# 74.net
KiCad netlist of a schematic drawn in EAGLE
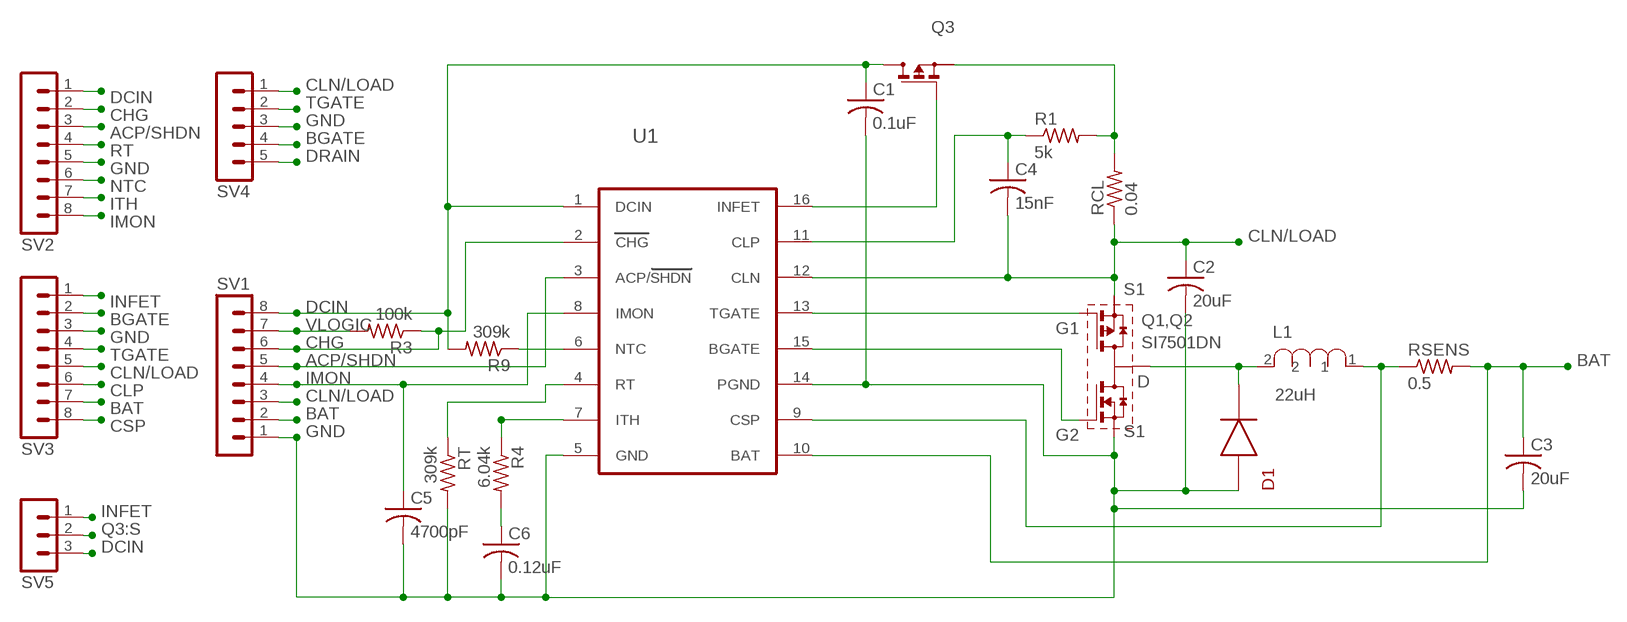
[diagram p0: schematic, sheet 1]

(export (version "E")
  (design (tool "Eeschema 10.0.6"))
  (components
    (comp (ref "C1")
      (value "0.1uF")
      (footprint "eagle-import:C1210")
      (libsource (lib "eagle-import") (part "C-USC1210"))
    )
    (comp (ref "C2")
      (value "20uF")
      (footprint "eagle-import:C1210")
      (libsource (lib "eagle-import") (part "C-USC1210"))
    )
    (comp (ref "C3")
      (value "20uF")
      (footprint "eagle-import:C1210")
      (libsource (lib "eagle-import") (part "C-USC1210"))
    )
    (comp (ref "C4")
      (value "15nF")
      (footprint "eagle-import:C1210")
      (libsource (lib "eagle-import") (part "C-USC1210"))
    )
    (comp (ref "C5")
      (value "4700pF")
      (footprint "eagle-import:C1210")
      (libsource (lib "eagle-import") (part "C-USC1210"))
    )
    (comp (ref "C6")
      (value "0.12uF")
      (footprint "eagle-import:C1210")
      (libsource (lib "eagle-import") (part "C-USC1210"))
    )
    (comp (ref "D1")
      (value "DIODE")
      (footprint "eagle-import:DIODE")
      (libsource (lib "eagle-import") (part "DIODE"))
    )
    (comp (ref "L1")
      (value "22uH")
      (footprint "eagle-import:POWERINDUCTOR")
      (libsource (lib "eagle-import") (part "SDR1005INDUCTOR"))
    )
    (comp (ref "Q1,Q2")
      (value "SI7501DN")
      (footprint "eagle-import:POWERPAK")
      (libsource (lib "eagle-import") (part "SI7501DN"))
    )
    (comp (ref "Q3")
      (value "MOSFET")
      (footprint "eagle-import:SOT-23")
      (libsource (lib "eagle-import") (part "MOSFET"))
    )
    (comp (ref "R1")
      (value "5k")
      (footprint "eagle-import:R1206")
      (libsource (lib "eagle-import") (part "R-US_R1206"))
    )
    (comp (ref "R3")
      (value "100k")
      (footprint "eagle-import:R1206")
      (libsource (lib "eagle-import") (part "R-US_R1206"))
    )
    (comp (ref "R4")
      (value "6.04k")
      (footprint "eagle-import:R1206")
      (libsource (lib "eagle-import") (part "R-US_R1206"))
    )
    (comp (ref "R9")
      (value "309k")
      (footprint "eagle-import:R1206")
      (libsource (lib "eagle-import") (part "R-US_R1206"))
    )
    (comp (ref "RCL")
      (value "0.04")
      (footprint "eagle-import:R1206")
      (libsource (lib "eagle-import") (part "R-US_R1206"))
    )
    (comp (ref "RSENS")
      (value "0.5")
      (footprint "eagle-import:0612_1632")
      (libsource (lib "eagle-import") (part "0612/1632"))
    )
    (comp (ref "RT")
      (value "309k")
      (footprint "eagle-import:R1206")
      (libsource (lib "eagle-import") (part "R-US_R1206"))
    )
    (comp (ref "SV1")
      (value "MA08-1")
      (footprint "eagle-import:MA08-1")
      (libsource (lib "eagle-import") (part "MA08-1"))
    )
    (comp (ref "SV2")
      (value "MA08-1")
      (footprint "eagle-import:MA08-1")
      (libsource (lib "eagle-import") (part "MA08-1"))
    )
    (comp (ref "SV3")
      (value "MA08-1")
      (footprint "eagle-import:MA08-1")
      (libsource (lib "eagle-import") (part "MA08-1"))
    )
    (comp (ref "SV4")
      (value "MA05-1")
      (footprint "eagle-import:MA05-1")
      (libsource (lib "eagle-import") (part "MA05-1"))
    )
    (comp (ref "SV5")
      (value "MA03-1")
      (footprint "eagle-import:MA03-1")
      (libsource (lib "eagle-import") (part "MA03-1"))
    )
    (comp (ref "U1")
      (value "LTC6004")
      (footprint "eagle-import:SSOP-16")
      (libsource (lib "eagle-import") (part "LTC6004"))
    )
  )
  (nets
    (net (code "1") (name "/ACP{slash}SHDN") (class "Default")
      (node (ref "SV1") (pin "5") (pinfunction "5_5") (pintype "passive"))
      (node (ref "SV2") (pin "3") (pinfunction "3_3") (pintype "passive"))
      (node (ref "U1") (pin "3") (pinfunction "ACP/SHDN_3") (pintype "power_in"))
    )
    (net (code "2") (name "/BAT") (class "Default")
      (node (ref "C3") (pin "1") (pinfunction "1_1") (pintype "passive"))
      (node (ref "RSENS") (pin "2") (pinfunction "2_2") (pintype "passive"))
      (node (ref "SV1") (pin "2") (pinfunction "2_2") (pintype "passive"))
      (node (ref "SV3") (pin "7") (pinfunction "7_7") (pintype "passive"))
      (node (ref "U1") (pin "10") (pinfunction "BAT_10") (pintype "power_in"))
    )
    (net (code "3") (name "/BGATE") (class "Default")
      (node (ref "Q1,Q2") (pin "G2") (pinfunction "G2_G2") (pintype "passive"))
      (node (ref "SV3") (pin "2") (pinfunction "2_2") (pintype "passive"))
      (node (ref "SV4") (pin "4") (pinfunction "4_4") (pintype "passive"))
      (node (ref "U1") (pin "15") (pinfunction "BGATE_15") (pintype "power_in"))
    )
    (net (code "4") (name "/CHG") (class "Default")
      (node (ref "R3") (pin "1") (pinfunction "1_1") (pintype "passive"))
      (node (ref "SV1") (pin "6") (pinfunction "6_6") (pintype "passive"))
      (node (ref "SV2") (pin "2") (pinfunction "2_2") (pintype "passive"))
      (node (ref "U1") (pin "2") (pinfunction "CHG_2") (pintype "power_in"))
    )
    (net (code "5") (name "/CLN{slash}LOAD") (class "Default")
      (node (ref "C2") (pin "1") (pinfunction "1_1") (pintype "passive"))
      (node (ref "C4") (pin "2") (pinfunction "2_2") (pintype "passive"))
      (node (ref "Q1,Q2") (pin "S1") (pinfunction "S1_S1") (pintype "passive"))
      (node (ref "RCL") (pin "1") (pinfunction "1_1") (pintype "passive"))
      (node (ref "SV1") (pin "3") (pinfunction "3_3") (pintype "passive"))
      (node (ref "SV3") (pin "5") (pinfunction "5_5") (pintype "passive"))
      (node (ref "SV4") (pin "1") (pinfunction "1_1") (pintype "passive"))
      (node (ref "U1") (pin "12") (pinfunction "CLN_12") (pintype "power_in"))
    )
    (net (code "6") (name "/CLP") (class "Default")
      (node (ref "C4") (pin "1") (pinfunction "1_1") (pintype "passive"))
      (node (ref "R1") (pin "1") (pinfunction "1_1") (pintype "passive"))
      (node (ref "SV3") (pin "6") (pinfunction "6_6") (pintype "passive"))
      (node (ref "U1") (pin "11") (pinfunction "CLP_11") (pintype "output"))
    )
    (net (code "7") (name "/CSP") (class "Default")
      (node (ref "L1") (pin "1") (pinfunction "1_1") (pintype "passive"))
      (node (ref "RSENS") (pin "1") (pinfunction "1_1") (pintype "passive"))
      (node (ref "SV3") (pin "8") (pinfunction "8_8") (pintype "passive"))
      (node (ref "U1") (pin "9") (pinfunction "CSP_9") (pintype "power_in"))
    )
    (net (code "8") (name "/DCIN") (class "Default")
      (node (ref "C1") (pin "1") (pinfunction "1_1") (pintype "passive"))
      (node (ref "Q3") (pin "DRAIN") (pinfunction "D_DRAIN") (pintype "passive"))
      (node (ref "R9") (pin "2") (pinfunction "2_2") (pintype "passive"))
      (node (ref "SV1") (pin "8") (pinfunction "8_8") (pintype "passive"))
      (node (ref "SV2") (pin "1") (pinfunction "1_1") (pintype "passive"))
      (node (ref "SV5") (pin "3") (pinfunction "3_3") (pintype "passive"))
      (node (ref "U1") (pin "1") (pinfunction "DCIN_1") (pintype "power_in"))
    )
    (net (code "9") (name "/DRAIN") (class "Default")
      (node (ref "D1") (pin "P$2") (pinfunction "2_P$2") (pintype "bidirectional"))
      (node (ref "L1") (pin "2") (pinfunction "2_2") (pintype "passive"))
      (node (ref "Q1,Q2") (pin "D") (pinfunction "D_D") (pintype "passive"))
      (node (ref "SV4") (pin "5") (pinfunction "5_5") (pintype "passive"))
    )
    (net (code "10") (name "/GND") (class "Default")
      (node (ref "C1") (pin "2") (pinfunction "2_2") (pintype "passive"))
      (node (ref "C2") (pin "2") (pinfunction "2_2") (pintype "passive"))
      (node (ref "C3") (pin "2") (pinfunction "2_2") (pintype "passive"))
      (node (ref "C5") (pin "2") (pinfunction "2_2") (pintype "passive"))
      (node (ref "C6") (pin "2") (pinfunction "2_2") (pintype "passive"))
      (node (ref "D1") (pin "P$1") (pinfunction "1_P$1") (pintype "bidirectional"))
      (node (ref "Q1,Q2") (pin "S2") (pinfunction "S2_S2") (pintype "passive"))
      (node (ref "RT") (pin "2") (pinfunction "2_2") (pintype "passive"))
      (node (ref "SV1") (pin "1") (pinfunction "1_1") (pintype "passive"))
      (node (ref "SV2") (pin "5") (pinfunction "5_5") (pintype "passive"))
      (node (ref "SV3") (pin "3") (pinfunction "3_3") (pintype "passive"))
      (node (ref "SV4") (pin "3") (pinfunction "3_3") (pintype "passive"))
      (node (ref "U1") (pin "14") (pinfunction "PGND_14") (pintype "power_in"))
      (node (ref "U1") (pin "5") (pinfunction "GND_5") (pintype "input"))
    )
    (net (code "11") (name "/IMON") (class "Default")
      (node (ref "C5") (pin "1") (pinfunction "1_1") (pintype "passive"))
      (node (ref "SV1") (pin "4") (pinfunction "4_4") (pintype "passive"))
      (node (ref "SV2") (pin "8") (pinfunction "8_8") (pintype "passive"))
      (node (ref "U1") (pin "8") (pinfunction "IMON_8") (pintype "power_in"))
    )
    (net (code "12") (name "/INFET") (class "Default")
      (node (ref "Q3") (pin "GATE") (pinfunction "G_GATE") (pintype "passive"))
      (node (ref "SV3") (pin "1") (pinfunction "1_1") (pintype "passive"))
      (node (ref "SV5") (pin "1") (pinfunction "1_1") (pintype "passive"))
      (node (ref "U1") (pin "16") (pinfunction "INFET_16") (pintype "output"))
    )
    (net (code "13") (name "/ITH") (class "Default")
      (node (ref "R4") (pin "1") (pinfunction "1_1") (pintype "passive"))
      (node (ref "SV2") (pin "7") (pinfunction "7_7") (pintype "passive"))
      (node (ref "U1") (pin "7") (pinfunction "ITH_7") (pintype "input"))
    )
    (net (code "14") (name "/NTC") (class "Default")
      (node (ref "R9") (pin "1") (pinfunction "1_1") (pintype "passive"))
      (node (ref "SV2") (pin "6") (pinfunction "6_6") (pintype "passive"))
      (node (ref "U1") (pin "6") (pinfunction "NTC_6") (pintype "power_in"))
    )
    (net (code "15") (name "/Q3:S") (class "Default")
      (node (ref "Q3") (pin "SOURCE") (pinfunction "S_SOURCE") (pintype "passive"))
      (node (ref "R1") (pin "2") (pinfunction "2_2") (pintype "passive"))
      (node (ref "RCL") (pin "2") (pinfunction "2_2") (pintype "passive"))
      (node (ref "SV5") (pin "2") (pinfunction "2_2") (pintype "passive"))
    )
    (net (code "16") (name "/RT") (class "Default")
      (node (ref "RT") (pin "1") (pinfunction "1_1") (pintype "passive"))
      (node (ref "SV2") (pin "4") (pinfunction "4_4") (pintype "passive"))
      (node (ref "U1") (pin "4") (pinfunction "RT_4") (pintype "input"))
    )
    (net (code "17") (name "/TGATE") (class "Default")
      (node (ref "Q1,Q2") (pin "G1") (pinfunction "G1_G1") (pintype "passive"))
      (node (ref "SV3") (pin "4") (pinfunction "4_4") (pintype "passive"))
      (node (ref "SV4") (pin "2") (pinfunction "2_2") (pintype "passive"))
      (node (ref "U1") (pin "13") (pinfunction "TGATE_13") (pintype "input"))
    )
    (net (code "18") (name "/VLOGIC") (class "Default")
      (node (ref "R3") (pin "2") (pinfunction "2_2") (pintype "passive"))
      (node (ref "SV1") (pin "7") (pinfunction "7_7") (pintype "passive"))
    )
    (net (code "19") (name "Net-(C6-Pad1)") (class "Default")
      (node (ref "C6") (pin "1") (pinfunction "1_1") (pintype "passive"))
      (node (ref "R4") (pin "2") (pinfunction "2_2") (pintype "passive"))
    )
  )
)
